# BMS_Enerdel_Adapter_rev7.net
KiCad netlist of a schematic drawn in EAGLE
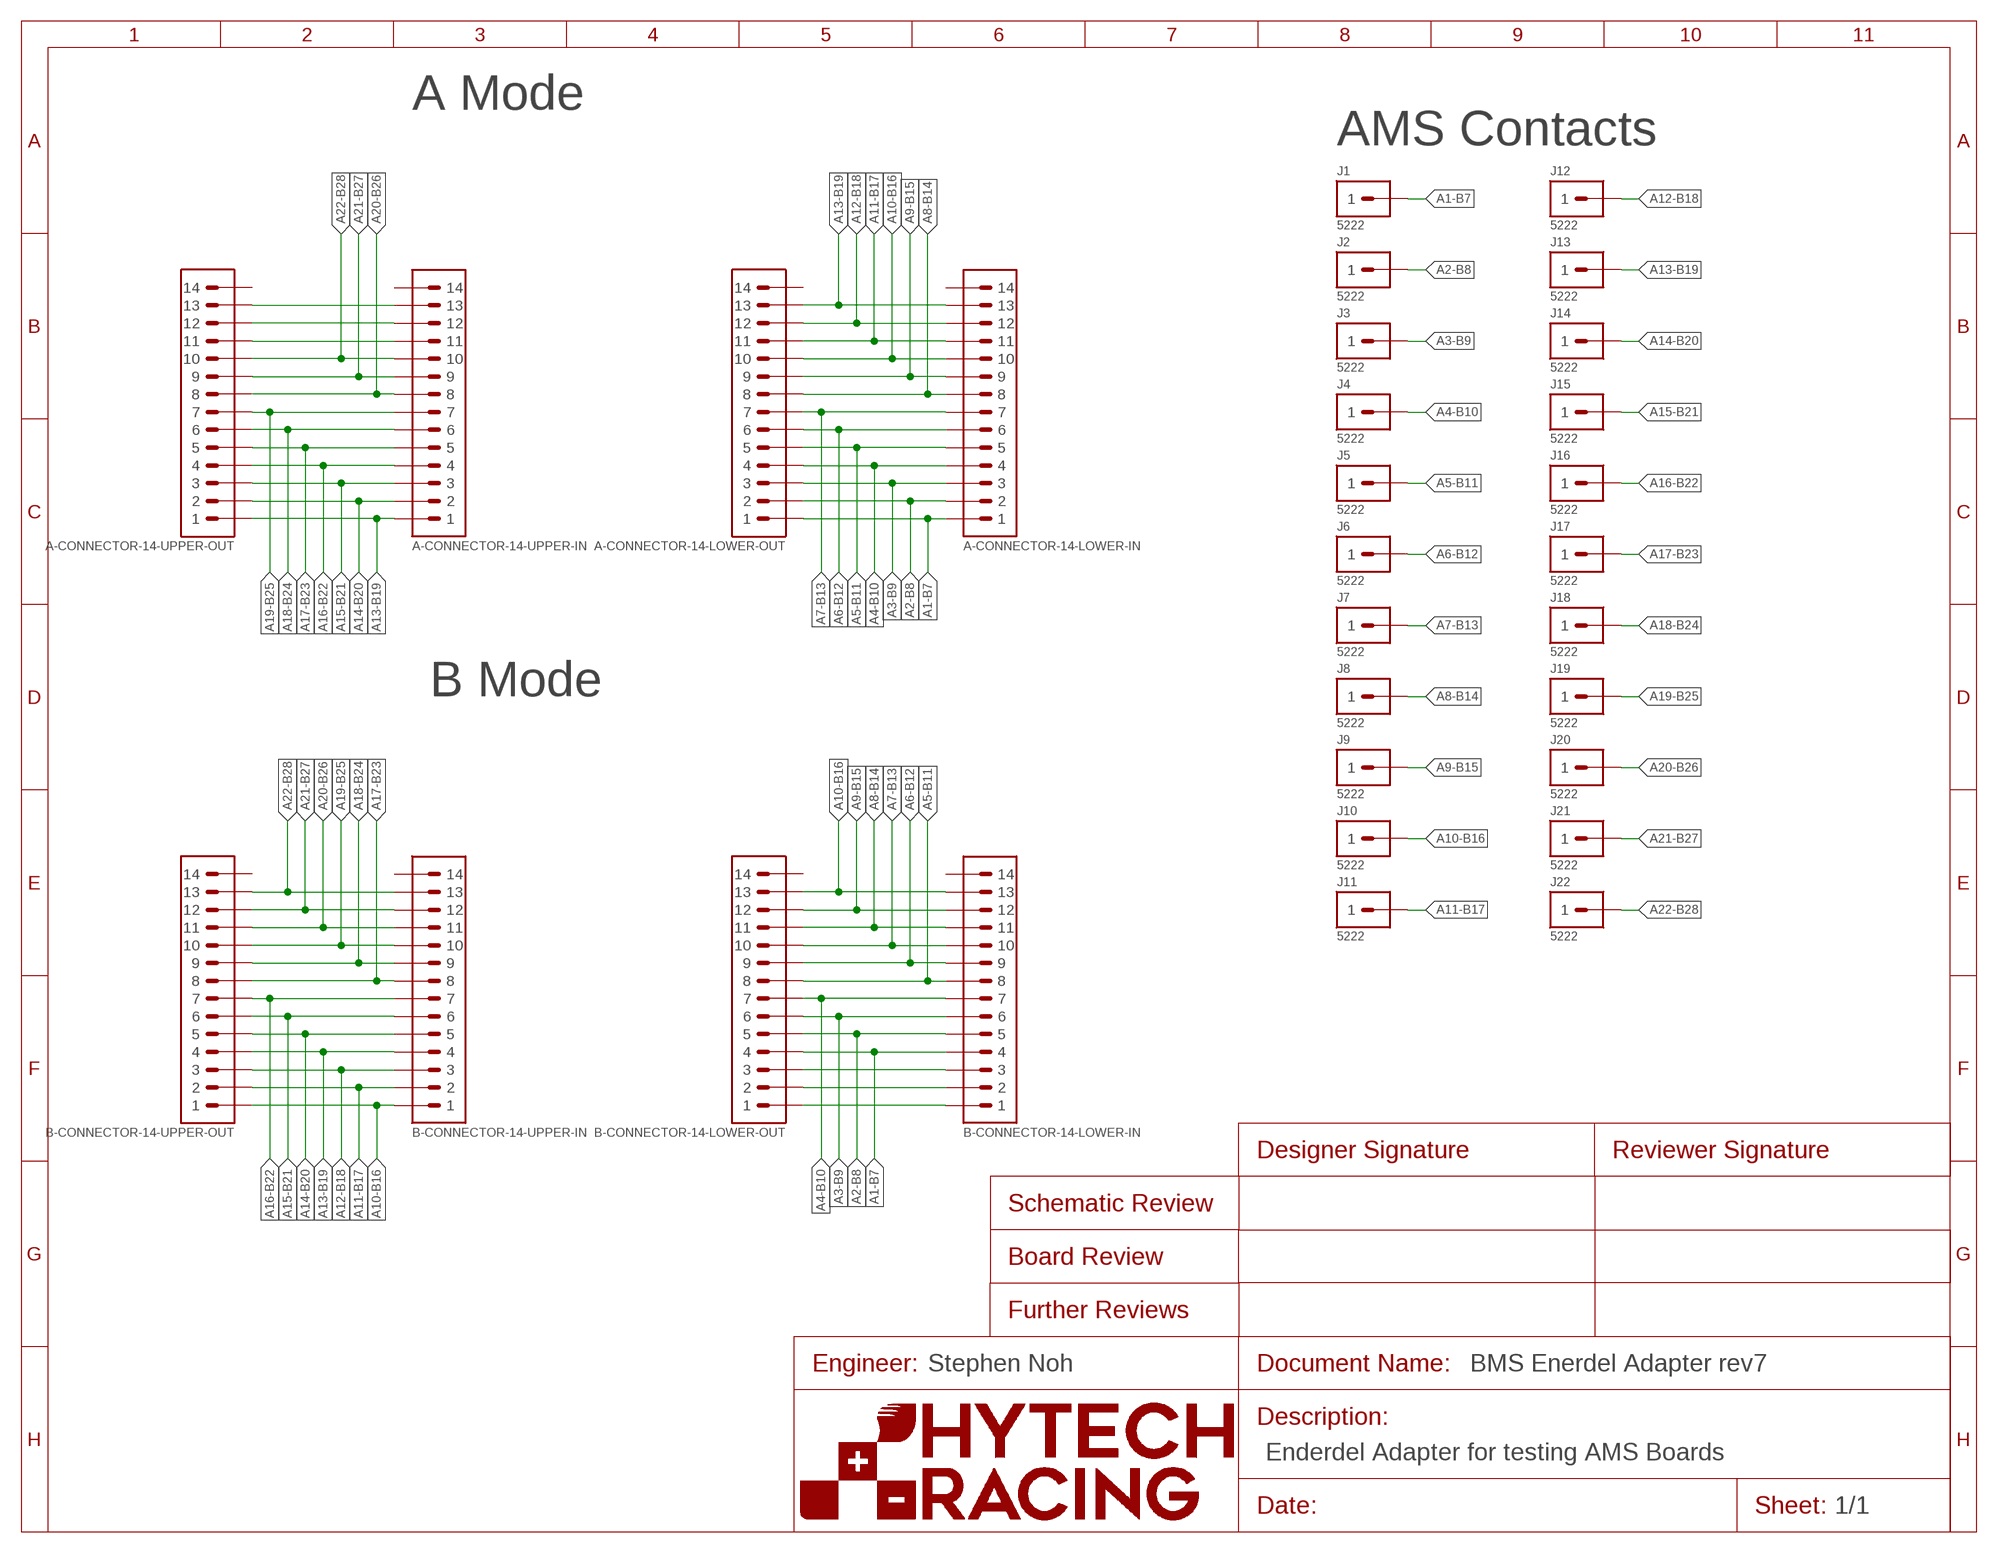
[diagram p0: schematic, sheet 1]

(export (version "E")
  (design (tool "Eeschema 10.0.6"))
  (components
    (comp (ref "A-CONNECTOR-14-LOWER-IN")
      (value "CONNECTOR-14_MINIFIT_")
      (footprint "eagle-import:MOLEX_MINIFIT_PTH_14")
      (libsource (lib "eagle-import") (part "CONNECTOR-14_?_MINIFIT"))
    )
    (comp (ref "A-CONNECTOR-14-LOWER-OUT")
      (value "CONNECTOR-14_MINIFIT_")
      (footprint "eagle-import:MOLEX_MINIFIT_PTH_14")
      (libsource (lib "eagle-import") (part "CONNECTOR-14_?_MINIFIT"))
    )
    (comp (ref "A-CONNECTOR-14-UPPER-IN")
      (value "CONNECTOR-14_NANOFIT_")
      (footprint "eagle-import:MOLEX_NANOFIT_PTH_14")
      (libsource (lib "eagle-import") (part "CONNECTOR-14_?_NANOFIT"))
    )
    (comp (ref "A-CONNECTOR-14-UPPER-OUT")
      (value "CONNECTOR-14_NANOFIT_")
      (footprint "eagle-import:MOLEX_NANOFIT_PTH_14")
      (libsource (lib "eagle-import") (part "CONNECTOR-14_?_NANOFIT"))
    )
    (comp (ref "B-CONNECTOR-14-LOWER-IN")
      (value "CONNECTOR-14_MINIFIT_")
      (footprint "eagle-import:MOLEX_MINIFIT_PTH_14")
      (libsource (lib "eagle-import") (part "CONNECTOR-14_?_MINIFIT"))
    )
    (comp (ref "B-CONNECTOR-14-LOWER-OUT")
      (value "CONNECTOR-14_MINIFIT_")
      (footprint "eagle-import:MOLEX_MINIFIT_PTH_14")
      (libsource (lib "eagle-import") (part "CONNECTOR-14_?_MINIFIT"))
    )
    (comp (ref "B-CONNECTOR-14-UPPER-IN")
      (value "CONNECTOR-14_NANOFIT_")
      (footprint "eagle-import:MOLEX_NANOFIT_PTH_14")
      (libsource (lib "eagle-import") (part "CONNECTOR-14_?_NANOFIT"))
    )
    (comp (ref "B-CONNECTOR-14-UPPER-OUT")
      (value "CONNECTOR-14_NANOFIT_")
      (footprint "eagle-import:MOLEX_NANOFIT_PTH_14")
      (libsource (lib "eagle-import") (part "CONNECTOR-14_?_NANOFIT"))
    )
    (comp (ref "J1")
      (value "CONNECTOR-1_5222_")
      (footprint "eagle-import:5222")
      (fields (field (name "MPN") "5222") (field (name "MANUFACTURER") "Keystone Electronics"))
      (libsource (lib "eagle-import") (part "CONNECTOR-1_?_5222"))
    )
    (comp (ref "J2")
      (value "CONNECTOR-1_5222_")
      (footprint "eagle-import:5222")
      (fields (field (name "MPN") "5222") (field (name "MANUFACTURER") "Keystone Electronics"))
      (libsource (lib "eagle-import") (part "CONNECTOR-1_?_5222"))
    )
    (comp (ref "J3")
      (value "CONNECTOR-1_5222_")
      (footprint "eagle-import:5222")
      (fields (field (name "MPN") "5222") (field (name "MANUFACTURER") "Keystone Electronics"))
      (libsource (lib "eagle-import") (part "CONNECTOR-1_?_5222"))
    )
    (comp (ref "J4")
      (value "CONNECTOR-1_5222_")
      (footprint "eagle-import:5222")
      (fields (field (name "MPN") "5222") (field (name "MANUFACTURER") "Keystone Electronics"))
      (libsource (lib "eagle-import") (part "CONNECTOR-1_?_5222"))
    )
    (comp (ref "J5")
      (value "CONNECTOR-1_5222_")
      (footprint "eagle-import:5222")
      (fields (field (name "MPN") "5222") (field (name "MANUFACTURER") "Keystone Electronics"))
      (libsource (lib "eagle-import") (part "CONNECTOR-1_?_5222"))
    )
    (comp (ref "J6")
      (value "CONNECTOR-1_5222_")
      (footprint "eagle-import:5222")
      (fields (field (name "MPN") "5222") (field (name "MANUFACTURER") "Keystone Electronics"))
      (libsource (lib "eagle-import") (part "CONNECTOR-1_?_5222"))
    )
    (comp (ref "J7")
      (value "CONNECTOR-1_5222_")
      (footprint "eagle-import:5222")
      (fields (field (name "MPN") "5222") (field (name "MANUFACTURER") "Keystone Electronics"))
      (libsource (lib "eagle-import") (part "CONNECTOR-1_?_5222"))
    )
    (comp (ref "J8")
      (value "CONNECTOR-1_5222_")
      (footprint "eagle-import:5222")
      (fields (field (name "MPN") "5222") (field (name "MANUFACTURER") "Keystone Electronics"))
      (libsource (lib "eagle-import") (part "CONNECTOR-1_?_5222"))
    )
    (comp (ref "J9")
      (value "CONNECTOR-1_5222_")
      (footprint "eagle-import:5222")
      (fields (field (name "MPN") "5222") (field (name "MANUFACTURER") "Keystone Electronics"))
      (libsource (lib "eagle-import") (part "CONNECTOR-1_?_5222"))
    )
    (comp (ref "J10")
      (value "CONNECTOR-1_5222_")
      (footprint "eagle-import:5222")
      (fields (field (name "MPN") "5222") (field (name "MANUFACTURER") "Keystone Electronics"))
      (libsource (lib "eagle-import") (part "CONNECTOR-1_?_5222"))
    )
    (comp (ref "J11")
      (value "CONNECTOR-1_5222_")
      (footprint "eagle-import:5222")
      (fields (field (name "MPN") "5222") (field (name "MANUFACTURER") "Keystone Electronics"))
      (libsource (lib "eagle-import") (part "CONNECTOR-1_?_5222"))
    )
    (comp (ref "J12")
      (value "CONNECTOR-1_5222_")
      (footprint "eagle-import:5222")
      (fields (field (name "MPN") "5222") (field (name "MANUFACTURER") "Keystone Electronics"))
      (libsource (lib "eagle-import") (part "CONNECTOR-1_?_5222"))
    )
    (comp (ref "J13")
      (value "CONNECTOR-1_5222_")
      (footprint "eagle-import:5222")
      (fields (field (name "MPN") "5222") (field (name "MANUFACTURER") "Keystone Electronics"))
      (libsource (lib "eagle-import") (part "CONNECTOR-1_?_5222"))
    )
    (comp (ref "J14")
      (value "CONNECTOR-1_5222_")
      (footprint "eagle-import:5222")
      (fields (field (name "MPN") "5222") (field (name "MANUFACTURER") "Keystone Electronics"))
      (libsource (lib "eagle-import") (part "CONNECTOR-1_?_5222"))
    )
    (comp (ref "J15")
      (value "CONNECTOR-1_5222_")
      (footprint "eagle-import:5222")
      (fields (field (name "MPN") "5222") (field (name "MANUFACTURER") "Keystone Electronics"))
      (libsource (lib "eagle-import") (part "CONNECTOR-1_?_5222"))
    )
    (comp (ref "J16")
      (value "CONNECTOR-1_5222_")
      (footprint "eagle-import:5222")
      (fields (field (name "MPN") "5222") (field (name "MANUFACTURER") "Keystone Electronics"))
      (libsource (lib "eagle-import") (part "CONNECTOR-1_?_5222"))
    )
    (comp (ref "J17")
      (value "CONNECTOR-1_5222_")
      (footprint "eagle-import:5222")
      (fields (field (name "MPN") "5222") (field (name "MANUFACTURER") "Keystone Electronics"))
      (libsource (lib "eagle-import") (part "CONNECTOR-1_?_5222"))
    )
    (comp (ref "J18")
      (value "CONNECTOR-1_5222_")
      (footprint "eagle-import:5222")
      (fields (field (name "MPN") "5222") (field (name "MANUFACTURER") "Keystone Electronics"))
      (libsource (lib "eagle-import") (part "CONNECTOR-1_?_5222"))
    )
    (comp (ref "J19")
      (value "CONNECTOR-1_5222_")
      (footprint "eagle-import:5222")
      (fields (field (name "MPN") "5222") (field (name "MANUFACTURER") "Keystone Electronics"))
      (libsource (lib "eagle-import") (part "CONNECTOR-1_?_5222"))
    )
    (comp (ref "J20")
      (value "CONNECTOR-1_5222_")
      (footprint "eagle-import:5222")
      (fields (field (name "MPN") "5222") (field (name "MANUFACTURER") "Keystone Electronics"))
      (libsource (lib "eagle-import") (part "CONNECTOR-1_?_5222"))
    )
    (comp (ref "J21")
      (value "CONNECTOR-1_5222_")
      (footprint "eagle-import:5222")
      (fields (field (name "MPN") "5222") (field (name "MANUFACTURER") "Keystone Electronics"))
      (libsource (lib "eagle-import") (part "CONNECTOR-1_?_5222"))
    )
    (comp (ref "J22")
      (value "CONNECTOR-1_5222_")
      (footprint "eagle-import:5222")
      (fields (field (name "MPN") "5222") (field (name "MANUFACTURER") "Keystone Electronics"))
      (libsource (lib "eagle-import") (part "CONNECTOR-1_?_5222"))
    )
  )
  (nets
    (net (code "1") (name "A1-B7") (class "Default")
      (node (ref "A-CONNECTOR-14-LOWER-IN") (pin "1") (pinfunction "1_1") (pintype "passive"))
      (node (ref "A-CONNECTOR-14-LOWER-OUT") (pin "1") (pinfunction "1_1") (pintype "passive"))
      (node (ref "B-CONNECTOR-14-LOWER-IN") (pin "4") (pinfunction "4_4") (pintype "passive"))
      (node (ref "B-CONNECTOR-14-LOWER-OUT") (pin "4") (pinfunction "4_4") (pintype "passive"))
      (node (ref "J1") (pin "1") (pinfunction "1_1") (pintype "passive"))
    )
    (net (code "2") (name "A2-B8") (class "Default")
      (node (ref "A-CONNECTOR-14-LOWER-IN") (pin "2") (pinfunction "2_2") (pintype "passive"))
      (node (ref "A-CONNECTOR-14-LOWER-OUT") (pin "2") (pinfunction "2_2") (pintype "passive"))
      (node (ref "B-CONNECTOR-14-LOWER-IN") (pin "5") (pinfunction "5_5") (pintype "passive"))
      (node (ref "B-CONNECTOR-14-LOWER-OUT") (pin "5") (pinfunction "5_5") (pintype "passive"))
      (node (ref "J2") (pin "1") (pinfunction "1_1") (pintype "passive"))
    )
    (net (code "3") (name "A3-B9") (class "Default")
      (node (ref "A-CONNECTOR-14-LOWER-IN") (pin "3") (pinfunction "3_3") (pintype "passive"))
      (node (ref "A-CONNECTOR-14-LOWER-OUT") (pin "3") (pinfunction "3_3") (pintype "passive"))
      (node (ref "B-CONNECTOR-14-LOWER-IN") (pin "6") (pinfunction "6_6") (pintype "passive"))
      (node (ref "B-CONNECTOR-14-LOWER-OUT") (pin "6") (pinfunction "6_6") (pintype "passive"))
      (node (ref "J3") (pin "1") (pinfunction "1_1") (pintype "passive"))
    )
    (net (code "4") (name "A4-B10") (class "Default")
      (node (ref "A-CONNECTOR-14-LOWER-IN") (pin "4") (pinfunction "4_4") (pintype "passive"))
      (node (ref "A-CONNECTOR-14-LOWER-OUT") (pin "4") (pinfunction "4_4") (pintype "passive"))
      (node (ref "B-CONNECTOR-14-LOWER-IN") (pin "7") (pinfunction "7_7") (pintype "passive"))
      (node (ref "B-CONNECTOR-14-LOWER-OUT") (pin "7") (pinfunction "7_7") (pintype "passive"))
      (node (ref "J4") (pin "1") (pinfunction "1_1") (pintype "passive"))
    )
    (net (code "5") (name "A5-B11") (class "Default")
      (node (ref "A-CONNECTOR-14-LOWER-IN") (pin "5") (pinfunction "5_5") (pintype "passive"))
      (node (ref "A-CONNECTOR-14-LOWER-OUT") (pin "5") (pinfunction "5_5") (pintype "passive"))
      (node (ref "B-CONNECTOR-14-LOWER-IN") (pin "8") (pinfunction "8_8") (pintype "passive"))
      (node (ref "B-CONNECTOR-14-LOWER-OUT") (pin "8") (pinfunction "8_8") (pintype "passive"))
      (node (ref "J5") (pin "1") (pinfunction "1_1") (pintype "passive"))
    )
    (net (code "6") (name "A6-B12") (class "Default")
      (node (ref "A-CONNECTOR-14-LOWER-IN") (pin "6") (pinfunction "6_6") (pintype "passive"))
      (node (ref "A-CONNECTOR-14-LOWER-OUT") (pin "6") (pinfunction "6_6") (pintype "passive"))
      (node (ref "B-CONNECTOR-14-LOWER-IN") (pin "9") (pinfunction "9_9") (pintype "passive"))
      (node (ref "B-CONNECTOR-14-LOWER-OUT") (pin "9") (pinfunction "9_9") (pintype "passive"))
      (node (ref "J6") (pin "1") (pinfunction "1_1") (pintype "passive"))
    )
    (net (code "7") (name "A7-B13") (class "Default")
      (node (ref "A-CONNECTOR-14-LOWER-IN") (pin "7") (pinfunction "7_7") (pintype "passive"))
      (node (ref "A-CONNECTOR-14-LOWER-OUT") (pin "7") (pinfunction "7_7") (pintype "passive"))
      (node (ref "B-CONNECTOR-14-LOWER-IN") (pin "10") (pinfunction "10_10") (pintype "passive"))
      (node (ref "B-CONNECTOR-14-LOWER-OUT") (pin "10") (pinfunction "10_10") (pintype "passive"))
      (node (ref "J7") (pin "1") (pinfunction "1_1") (pintype "passive"))
    )
    (net (code "8") (name "A8-B14") (class "Default")
      (node (ref "A-CONNECTOR-14-LOWER-IN") (pin "8") (pinfunction "8_8") (pintype "passive"))
      (node (ref "A-CONNECTOR-14-LOWER-OUT") (pin "8") (pinfunction "8_8") (pintype "passive"))
      (node (ref "B-CONNECTOR-14-LOWER-IN") (pin "11") (pinfunction "11_11") (pintype "passive"))
      (node (ref "B-CONNECTOR-14-LOWER-OUT") (pin "11") (pinfunction "11_11") (pintype "passive"))
      (node (ref "J8") (pin "1") (pinfunction "1_1") (pintype "passive"))
    )
    (net (code "9") (name "A9-B15") (class "Default")
      (node (ref "A-CONNECTOR-14-LOWER-IN") (pin "9") (pinfunction "9_9") (pintype "passive"))
      (node (ref "A-CONNECTOR-14-LOWER-OUT") (pin "9") (pinfunction "9_9") (pintype "passive"))
      (node (ref "B-CONNECTOR-14-LOWER-IN") (pin "12") (pinfunction "12_12") (pintype "passive"))
      (node (ref "B-CONNECTOR-14-LOWER-OUT") (pin "12") (pinfunction "12_12") (pintype "passive"))
      (node (ref "J9") (pin "1") (pinfunction "1_1") (pintype "passive"))
    )
    (net (code "10") (name "A10-B16") (class "Default")
      (node (ref "A-CONNECTOR-14-LOWER-IN") (pin "10") (pinfunction "10_10") (pintype "passive"))
      (node (ref "A-CONNECTOR-14-LOWER-OUT") (pin "10") (pinfunction "10_10") (pintype "passive"))
      (node (ref "B-CONNECTOR-14-LOWER-IN") (pin "13") (pinfunction "13_13") (pintype "passive"))
      (node (ref "B-CONNECTOR-14-LOWER-OUT") (pin "13") (pinfunction "13_13") (pintype "passive"))
      (node (ref "B-CONNECTOR-14-UPPER-IN") (pin "1") (pinfunction "1_1") (pintype "passive"))
      (node (ref "B-CONNECTOR-14-UPPER-OUT") (pin "1") (pinfunction "1_1") (pintype "passive"))
      (node (ref "J10") (pin "1") (pinfunction "1_1") (pintype "passive"))
    )
    (net (code "11") (name "A11-B17") (class "Default")
      (node (ref "A-CONNECTOR-14-LOWER-IN") (pin "11") (pinfunction "11_11") (pintype "passive"))
      (node (ref "A-CONNECTOR-14-LOWER-OUT") (pin "11") (pinfunction "11_11") (pintype "passive"))
      (node (ref "B-CONNECTOR-14-UPPER-IN") (pin "2") (pinfunction "2_2") (pintype "passive"))
      (node (ref "B-CONNECTOR-14-UPPER-OUT") (pin "2") (pinfunction "2_2") (pintype "passive"))
      (node (ref "J11") (pin "1") (pinfunction "1_1") (pintype "passive"))
    )
    (net (code "12") (name "A12-B18") (class "Default")
      (node (ref "A-CONNECTOR-14-LOWER-IN") (pin "12") (pinfunction "12_12") (pintype "passive"))
      (node (ref "A-CONNECTOR-14-LOWER-OUT") (pin "12") (pinfunction "12_12") (pintype "passive"))
      (node (ref "B-CONNECTOR-14-UPPER-IN") (pin "3") (pinfunction "3_3") (pintype "passive"))
      (node (ref "B-CONNECTOR-14-UPPER-OUT") (pin "3") (pinfunction "3_3") (pintype "passive"))
      (node (ref "J12") (pin "1") (pinfunction "1_1") (pintype "passive"))
    )
    (net (code "13") (name "A13-B19") (class "Default")
      (node (ref "A-CONNECTOR-14-LOWER-IN") (pin "13") (pinfunction "13_13") (pintype "passive"))
      (node (ref "A-CONNECTOR-14-LOWER-OUT") (pin "13") (pinfunction "13_13") (pintype "passive"))
      (node (ref "A-CONNECTOR-14-UPPER-IN") (pin "1") (pinfunction "1_1") (pintype "passive"))
      (node (ref "A-CONNECTOR-14-UPPER-OUT") (pin "1") (pinfunction "1_1") (pintype "passive"))
      (node (ref "B-CONNECTOR-14-UPPER-IN") (pin "4") (pinfunction "4_4") (pintype "passive"))
      (node (ref "B-CONNECTOR-14-UPPER-OUT") (pin "4") (pinfunction "4_4") (pintype "passive"))
      (node (ref "J13") (pin "1") (pinfunction "1_1") (pintype "passive"))
    )
    (net (code "14") (name "A14-B20") (class "Default")
      (node (ref "A-CONNECTOR-14-UPPER-IN") (pin "2") (pinfunction "2_2") (pintype "passive"))
      (node (ref "A-CONNECTOR-14-UPPER-OUT") (pin "2") (pinfunction "2_2") (pintype "passive"))
      (node (ref "B-CONNECTOR-14-UPPER-IN") (pin "5") (pinfunction "5_5") (pintype "passive"))
      (node (ref "B-CONNECTOR-14-UPPER-OUT") (pin "5") (pinfunction "5_5") (pintype "passive"))
      (node (ref "J14") (pin "1") (pinfunction "1_1") (pintype "passive"))
    )
    (net (code "15") (name "A15-B21") (class "Default")
      (node (ref "A-CONNECTOR-14-UPPER-IN") (pin "3") (pinfunction "3_3") (pintype "passive"))
      (node (ref "A-CONNECTOR-14-UPPER-OUT") (pin "3") (pinfunction "3_3") (pintype "passive"))
      (node (ref "B-CONNECTOR-14-UPPER-IN") (pin "6") (pinfunction "6_6") (pintype "passive"))
      (node (ref "B-CONNECTOR-14-UPPER-OUT") (pin "6") (pinfunction "6_6") (pintype "passive"))
      (node (ref "J15") (pin "1") (pinfunction "1_1") (pintype "passive"))
    )
    (net (code "16") (name "A16-B22") (class "Default")
      (node (ref "A-CONNECTOR-14-UPPER-IN") (pin "4") (pinfunction "4_4") (pintype "passive"))
      (node (ref "A-CONNECTOR-14-UPPER-OUT") (pin "4") (pinfunction "4_4") (pintype "passive"))
      (node (ref "B-CONNECTOR-14-UPPER-IN") (pin "7") (pinfunction "7_7") (pintype "passive"))
      (node (ref "B-CONNECTOR-14-UPPER-OUT") (pin "7") (pinfunction "7_7") (pintype "passive"))
      (node (ref "J16") (pin "1") (pinfunction "1_1") (pintype "passive"))
    )
    (net (code "17") (name "A17-B23") (class "Default")
      (node (ref "A-CONNECTOR-14-UPPER-IN") (pin "5") (pinfunction "5_5") (pintype "passive"))
      (node (ref "A-CONNECTOR-14-UPPER-OUT") (pin "5") (pinfunction "5_5") (pintype "passive"))
      (node (ref "B-CONNECTOR-14-UPPER-IN") (pin "8") (pinfunction "8_8") (pintype "passive"))
      (node (ref "B-CONNECTOR-14-UPPER-OUT") (pin "8") (pinfunction "8_8") (pintype "passive"))
      (node (ref "J17") (pin "1") (pinfunction "1_1") (pintype "passive"))
    )
    (net (code "18") (name "A18-B24") (class "Default")
      (node (ref "A-CONNECTOR-14-UPPER-IN") (pin "6") (pinfunction "6_6") (pintype "passive"))
      (node (ref "A-CONNECTOR-14-UPPER-OUT") (pin "6") (pinfunction "6_6") (pintype "passive"))
      (node (ref "B-CONNECTOR-14-UPPER-IN") (pin "9") (pinfunction "9_9") (pintype "passive"))
      (node (ref "B-CONNECTOR-14-UPPER-OUT") (pin "9") (pinfunction "9_9") (pintype "passive"))
      (node (ref "J18") (pin "1") (pinfunction "1_1") (pintype "passive"))
    )
    (net (code "19") (name "A19-B25") (class "Default")
      (node (ref "A-CONNECTOR-14-UPPER-IN") (pin "7") (pinfunction "7_7") (pintype "passive"))
      (node (ref "A-CONNECTOR-14-UPPER-OUT") (pin "7") (pinfunction "7_7") (pintype "passive"))
      (node (ref "B-CONNECTOR-14-UPPER-IN") (pin "10") (pinfunction "10_10") (pintype "passive"))
      (node (ref "B-CONNECTOR-14-UPPER-OUT") (pin "10") (pinfunction "10_10") (pintype "passive"))
      (node (ref "J19") (pin "1") (pinfunction "1_1") (pintype "passive"))
    )
    (net (code "20") (name "A20-B26") (class "Default")
      (node (ref "A-CONNECTOR-14-UPPER-IN") (pin "8") (pinfunction "8_8") (pintype "passive"))
      (node (ref "A-CONNECTOR-14-UPPER-OUT") (pin "8") (pinfunction "8_8") (pintype "passive"))
      (node (ref "B-CONNECTOR-14-UPPER-IN") (pin "11") (pinfunction "11_11") (pintype "passive"))
      (node (ref "B-CONNECTOR-14-UPPER-OUT") (pin "11") (pinfunction "11_11") (pintype "passive"))
      (node (ref "J20") (pin "1") (pinfunction "1_1") (pintype "passive"))
    )
    (net (code "21") (name "A21-B27") (class "Default")
      (node (ref "A-CONNECTOR-14-UPPER-IN") (pin "9") (pinfunction "9_9") (pintype "passive"))
      (node (ref "A-CONNECTOR-14-UPPER-OUT") (pin "9") (pinfunction "9_9") (pintype "passive"))
      (node (ref "B-CONNECTOR-14-UPPER-IN") (pin "12") (pinfunction "12_12") (pintype "passive"))
      (node (ref "B-CONNECTOR-14-UPPER-OUT") (pin "12") (pinfunction "12_12") (pintype "passive"))
      (node (ref "J21") (pin "1") (pinfunction "1_1") (pintype "passive"))
    )
    (net (code "22") (name "A22-B28") (class "Default")
      (node (ref "A-CONNECTOR-14-UPPER-IN") (pin "10") (pinfunction "10_10") (pintype "passive"))
      (node (ref "A-CONNECTOR-14-UPPER-OUT") (pin "10") (pinfunction "10_10") (pintype "passive"))
      (node (ref "B-CONNECTOR-14-UPPER-IN") (pin "13") (pinfunction "13_13") (pintype "passive"))
      (node (ref "B-CONNECTOR-14-UPPER-OUT") (pin "13") (pinfunction "13_13") (pintype "passive"))
      (node (ref "J22") (pin "1") (pinfunction "1_1") (pintype "passive"))
    )
    (net (code "23") (name "Net-(A-CONNECTOR-14-UPPER-IN-Pad11)") (class "Default")
      (node (ref "A-CONNECTOR-14-UPPER-IN") (pin "11") (pinfunction "11_11") (pintype "passive"))
      (node (ref "A-CONNECTOR-14-UPPER-OUT") (pin "11") (pinfunction "11_11") (pintype "passive"))
    )
    (net (code "24") (name "Net-(A-CONNECTOR-14-UPPER-IN-Pad12)") (class "Default")
      (node (ref "A-CONNECTOR-14-UPPER-IN") (pin "12") (pinfunction "12_12") (pintype "passive"))
      (node (ref "A-CONNECTOR-14-UPPER-OUT") (pin "12") (pinfunction "12_12") (pintype "passive"))
    )
    (net (code "25") (name "Net-(A-CONNECTOR-14-UPPER-IN-Pad13)") (class "Default")
      (node (ref "A-CONNECTOR-14-UPPER-IN") (pin "13") (pinfunction "13_13") (pintype "passive"))
      (node (ref "A-CONNECTOR-14-UPPER-OUT") (pin "13") (pinfunction "13_13") (pintype "passive"))
    )
    (net (code "26") (name "Net-(B-CONNECTOR-14-LOWER-IN-Pad1)") (class "Default")
      (node (ref "B-CONNECTOR-14-LOWER-IN") (pin "1") (pinfunction "1_1") (pintype "passive"))
      (node (ref "B-CONNECTOR-14-LOWER-OUT") (pin "1") (pinfunction "1_1") (pintype "passive"))
    )
    (net (code "27") (name "Net-(B-CONNECTOR-14-LOWER-IN-Pad2)") (class "Default")
      (node (ref "B-CONNECTOR-14-LOWER-IN") (pin "2") (pinfunction "2_2") (pintype "passive"))
      (node (ref "B-CONNECTOR-14-LOWER-OUT") (pin "2") (pinfunction "2_2") (pintype "passive"))
    )
    (net (code "28") (name "Net-(B-CONNECTOR-14-LOWER-IN-Pad3)") (class "Default")
      (node (ref "B-CONNECTOR-14-LOWER-IN") (pin "3") (pinfunction "3_3") (pintype "passive"))
      (node (ref "B-CONNECTOR-14-LOWER-OUT") (pin "3") (pinfunction "3_3") (pintype "passive"))
    )
    (net (code "29") (name "unconnected-(A-CONNECTOR-14-LOWER-IN-Pad14)") (class "Default")
      (node (ref "A-CONNECTOR-14-LOWER-IN") (pin "14") (pinfunction "14_14") (pintype "passive"))
    )
    (net (code "30") (name "unconnected-(A-CONNECTOR-14-LOWER-OUT-Pad14)") (class "Default")
      (node (ref "A-CONNECTOR-14-LOWER-OUT") (pin "14") (pinfunction "14_14") (pintype "passive"))
    )
    (net (code "31") (name "unconnected-(A-CONNECTOR-14-UPPER-IN-Pad14)") (class "Default")
      (node (ref "A-CONNECTOR-14-UPPER-IN") (pin "14") (pinfunction "14_14") (pintype "passive"))
    )
    (net (code "32") (name "unconnected-(A-CONNECTOR-14-UPPER-OUT-Pad14)") (class "Default")
      (node (ref "A-CONNECTOR-14-UPPER-OUT") (pin "14") (pinfunction "14_14") (pintype "passive"))
    )
    (net (code "33") (name "unconnected-(B-CONNECTOR-14-LOWER-IN-Pad14)") (class "Default")
      (node (ref "B-CONNECTOR-14-LOWER-IN") (pin "14") (pinfunction "14_14") (pintype "passive"))
    )
    (net (code "34") (name "unconnected-(B-CONNECTOR-14-LOWER-OUT-Pad14)") (class "Default")
      (node (ref "B-CONNECTOR-14-LOWER-OUT") (pin "14") (pinfunction "14_14") (pintype "passive"))
    )
    (net (code "35") (name "unconnected-(B-CONNECTOR-14-UPPER-IN-Pad14)") (class "Default")
      (node (ref "B-CONNECTOR-14-UPPER-IN") (pin "14") (pinfunction "14_14") (pintype "passive"))
    )
    (net (code "36") (name "unconnected-(B-CONNECTOR-14-UPPER-OUT-Pad14)") (class "Default")
      (node (ref "B-CONNECTOR-14-UPPER-OUT") (pin "14") (pinfunction "14_14") (pintype "passive"))
    )
  )
)
